# SCH_-_ROBOTIC_ARM.net
KiCad netlist of a schematic drawn in Altium Designer
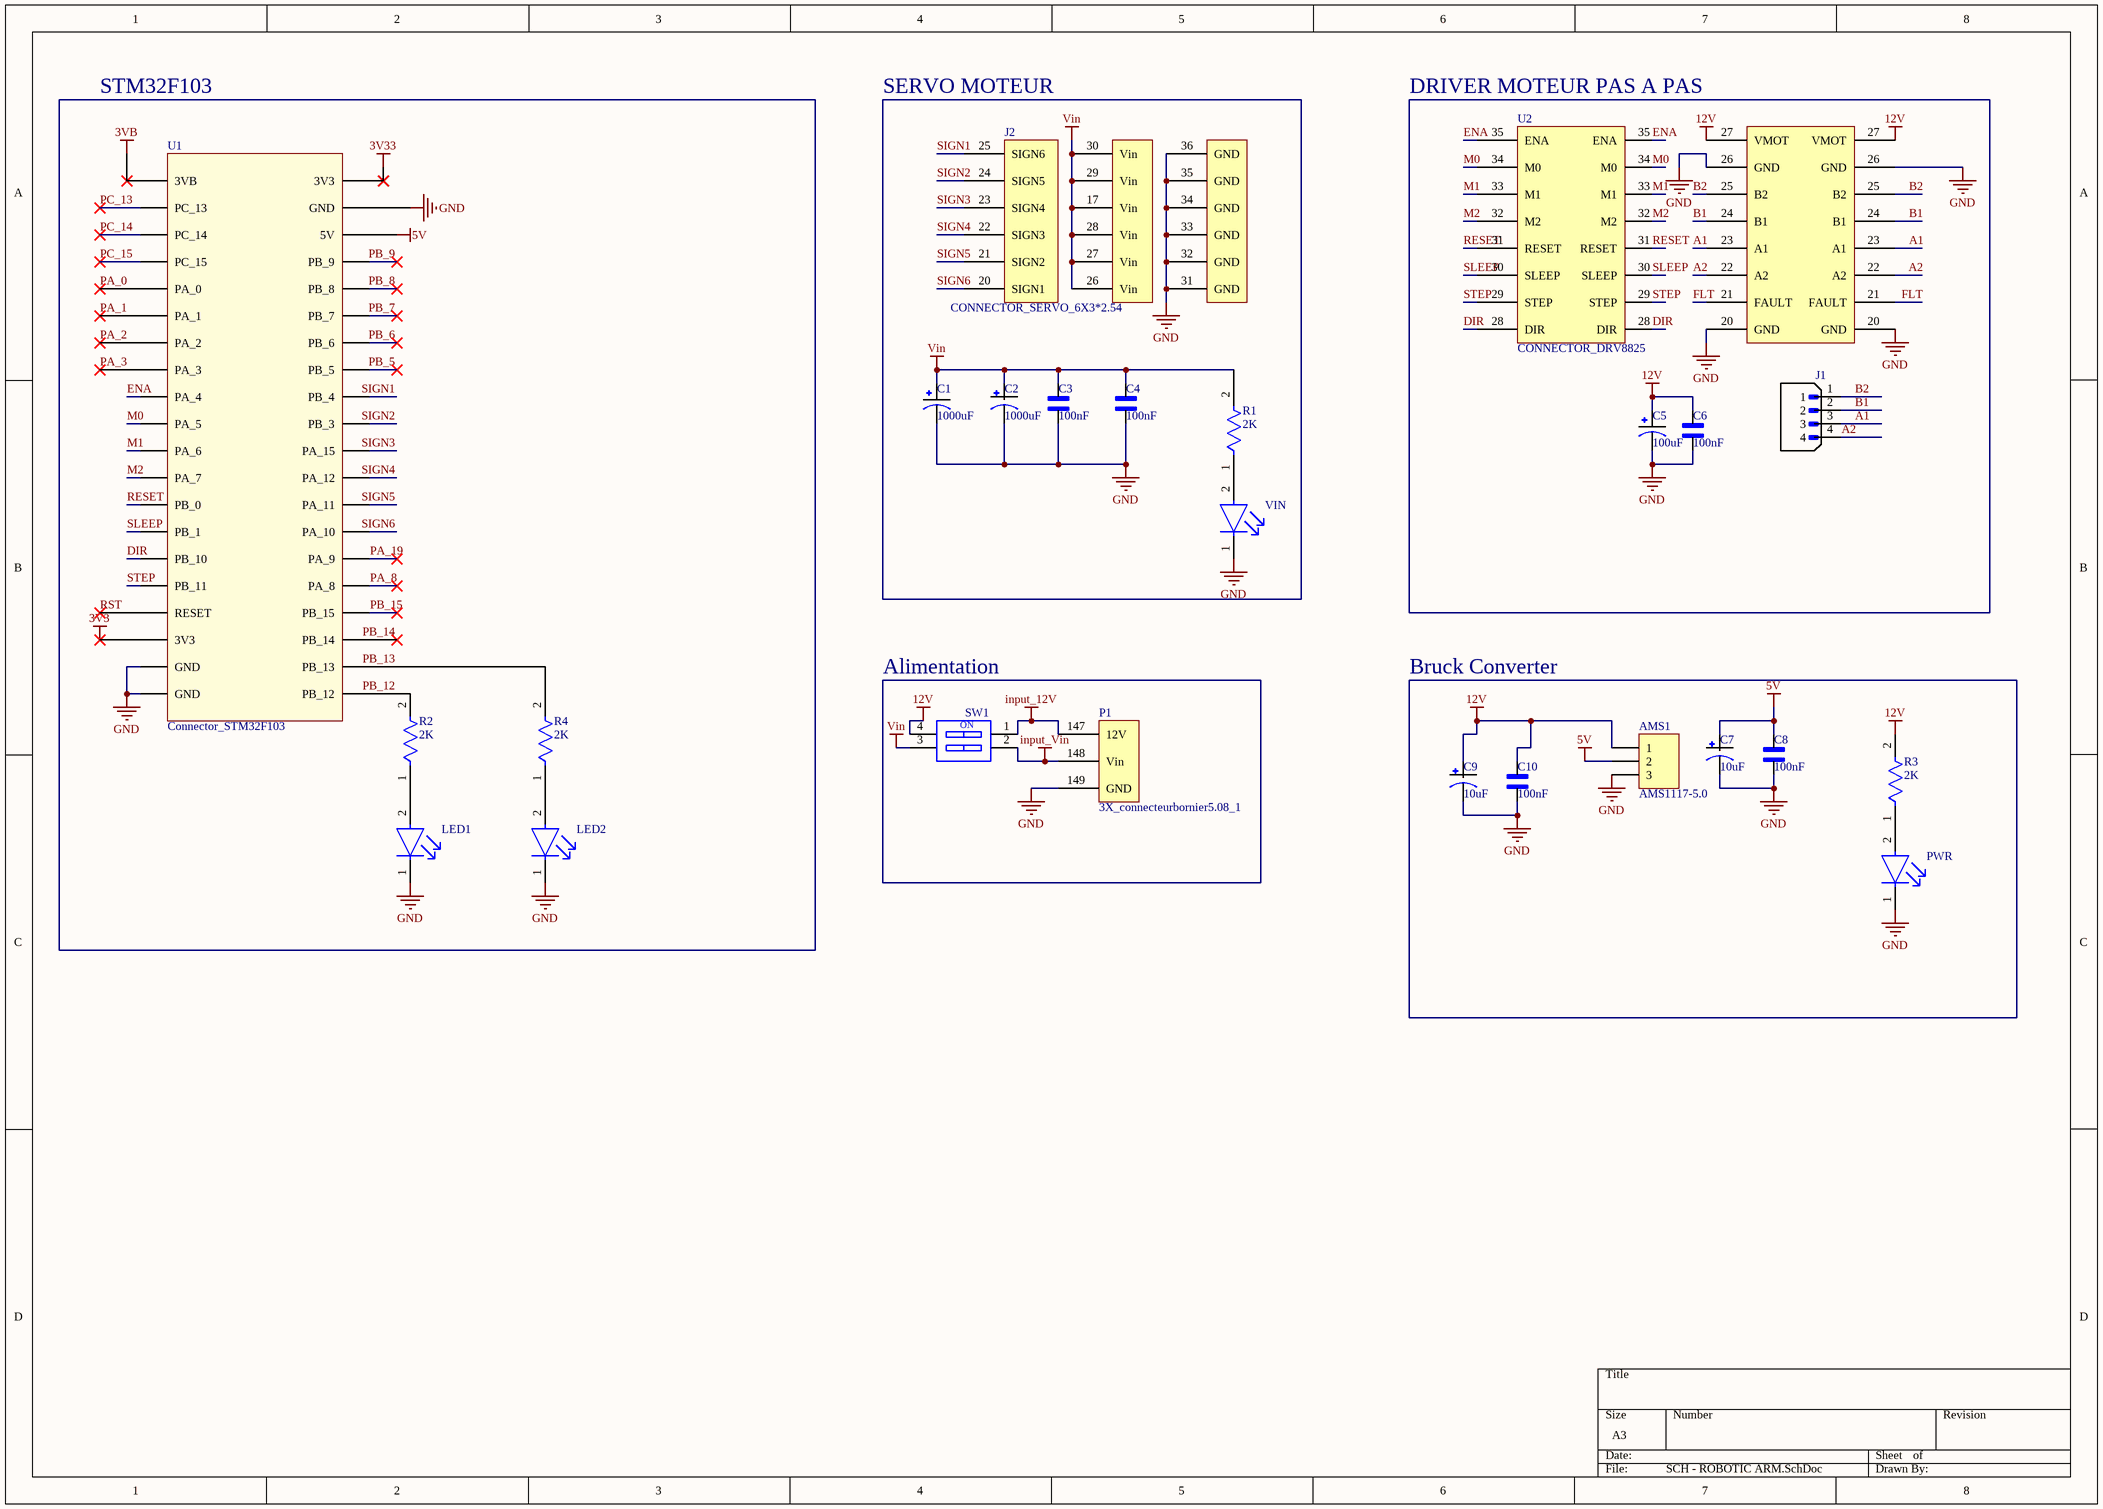
[diagram p0: SCH - ROBOTIC ARM.SchDoc]

(export (version "E")
  (design (tool "Eeschema 10.0.6"))
  (components
    (comp (ref "AMS1")
      (value "AMS1117-5.0")
      (footprint "HDR1X3")
      (description "Header, 3-Pin")
      (fields (field (name "PUBLISHER") "Altium Limited"))
      (libsource (lib "Miscellaneous Connectors") (part "Header 3"))
    )
    (comp (ref "C1")
      (value "1000uF")
      (footprint "*CAPPRD500W60D1000H1600_ECA1CM102(Primary)")
      (description "1000ÂµF 16V Aluminum Electrolytic Capacitors Radial, Can 2000 Hrs @ 85Â°C")
      (fields (field (name "MF") "Panasonic") (field (name "MP") "ECA1CM102"))
      (libsource (lib "Schlib1") (part "ECA1CM102"))
    )
    (comp (ref "C2")
      (value "1000uF")
      (footprint "*CAPPRD200W50D550H1250")
      (description "10 ÂµF 25 V Aluminum Electrolytic Capacitors Radial, Can - 2000 Hrs @ 85Â°C")
      (fields (field (name "MF") "Nichicon") (field (name "MP") "UVR1E100MDD"))
      (libsource (lib "Schlib1") (part "UVR1E100MDD"))
    )
    (comp (ref "C3")
      (value "100nF")
      (footprint "*CAPRR508W50L508T317H508")
      (description "SR Series 5.08x5.08 mm 100 nF 50 V Â±20% Tol. Z5U Radial Lead/SkyCapÂ®")
      (fields (field (name "MF") "AVX") (field (name "MP") "SR215E104MARTR1"))
      (libsource (lib "Schlib1") (part "SR215E104MARTR1"))
    )
    (comp (ref "C4")
      (value "100nF")
      (footprint "*CAPRR508W50L508T317H508")
      (description "SR Series 5.08x5.08 mm 100 nF 50 V Â±20% Tol. Z5U Radial Lead/SkyCapÂ®")
      (fields (field (name "MF") "AVX") (field (name "MP") "SR215E104MARTR1"))
      (libsource (lib "Schlib1") (part "SR215E104MARTR1"))
    )
    (comp (ref "C5")
      (value "100uF")
      (footprint "*CAPPRD500W60D1000H1600_ECA1CM102(Primary)")
      (description "1000ÂµF 16V Aluminum Electrolytic Capacitors Radial, Can 2000 Hrs @ 85Â°C")
      (fields (field (name "MF") "Panasonic") (field (name "MP") "ECA1CM102"))
      (libsource (lib "Schlib1") (part "ECA1CM102"))
    )
    (comp (ref "C6")
      (value "100nF")
      (footprint "*CAPRR508W50L508T317H508")
      (description "SR Series 5.08x5.08 mm 100 nF 50 V Â±20% Tol. Z5U Radial Lead/SkyCapÂ®")
      (fields (field (name "MF") "AVX") (field (name "MP") "SR215E104MARTR1"))
      (libsource (lib "Schlib1") (part "SR215E104MARTR1"))
    )
    (comp (ref "C7")
      (value "10uF")
      (footprint "*CAPPRD200W50D550H1250")
      (description "10 ÂµF 25 V Aluminum Electrolytic Capacitors Radial, Can - 2000 Hrs @ 85Â°C")
      (fields (field (name "MF") "Nichicon") (field (name "MP") "UVR1E100MDD"))
      (libsource (lib "Schlib1") (part "UVR1E100MDD"))
    )
    (comp (ref "C8")
      (value "100nF")
      (footprint "*CAPRR508W50L508T317H508")
      (description "SR Series 5.08x5.08 mm 100 nF 50 V Â±20% Tol. Z5U Radial Lead/SkyCapÂ®")
      (fields (field (name "MF") "AVX") (field (name "MP") "SR215E104MARTR1"))
      (libsource (lib "Schlib1") (part "SR215E104MARTR1"))
    )
    (comp (ref "C9")
      (value "10uF")
      (footprint "*CAPPRD200W50D550H1250")
      (description "10 ÂµF 25 V Aluminum Electrolytic Capacitors Radial, Can - 2000 Hrs @ 85Â°C")
      (fields (field (name "MF") "Nichicon") (field (name "MP") "UVR1E100MDD"))
      (libsource (lib "Schlib1") (part "UVR1E100MDD"))
    )
    (comp (ref "C10")
      (value "100nF")
      (footprint "*CAPPRD200W50D550H1250")
      (description "SR Series 5.08x5.08 mm 100 nF 50 V Â±20% Tol. Z5U Radial Lead/SkyCapÂ®")
      (fields (field (name "MF") "AVX") (field (name "MP") "SR215E104MARTR1"))
      (libsource (lib "Schlib1") (part "SR215E104MARTR1"))
    )
    (comp (ref "J1")
      (value "B4B-XH-A(LF)(SN)")
      (footprint "*JST_B4B-XH-A(LF)(SN)")
      (fields (field (name "MF") "JST") (field (name "MP") "B4B-XH-A  (LF)(SN)"))
      (libsource (lib "Schlib1") (part "B4B-XH-A(LF)(SN)"))
    )
    (comp (ref "J2")
      (value "CONNECTOR_SERVO_6X3*2.54")
      (footprint "CONNECTOR_SERVO_6X3*2.54")
      (libsource (lib "Schlib1") (part "CONNECTOR_SERVO_6X3*2.54"))
    )
    (comp (ref "LED1")
      (value "LED1")
      (footprint "FP-VSLB3940-MFG")
      (description "VSLB3940 940 nm 100 mA ±22° Through Hole High Speed Infrared Emitting Diode - T-1")
      (libsource (lib "Altium Content Vault") (part "8706943c75ba83719d021d2fdc84c58"))
    )
    (comp (ref "LED2")
      (value "LED1")
      (footprint "FP-VSLB3940-MFG")
      (description "VSLB3940 940 nm 100 mA ±22° Through Hole High Speed Infrared Emitting Diode - T-1")
      (libsource (lib "Altium Content Vault") (part "8706943c75ba83719d021d2fdc84c58"))
    )
    (comp (ref "P1")
      (value "3X_connecteurbornier5.08_1")
      (footprint "3X_connecteur_bornier_5.08")
      (libsource (lib "Schlib1") (part "3X_connecteurbornier5.08_1"))
    )
    (comp (ref "PWR")
      (value "LED1")
      (footprint "FP-VSLB3940-MFG")
      (description "VSLB3940 940 nm 100 mA ±22° Through Hole High Speed Infrared Emitting Diode - T-1")
      (libsource (lib "Altium Content Vault") (part "8706943c75ba83719d021d2fdc84c58"))
    )
    (comp (ref "R1")
      (value "2K")
      (footprint "FP-CMF50-0")
      (description "RN50C9532FB14 RN50 Series 0.05 W 95.3 kOhm ± 1% ±50 ppm/°C Axial Metal Film Resistor")
      (fields (field (name "TOLERANCE") "1%"))
      (libsource (lib "Altium Content Vault") (part "1029c3af85768c4190bb7ad29bc67b5"))
    )
    (comp (ref "R2")
      (value "2K")
      (footprint "FP-CMF50-0")
      (description "RN50C9532FB14 RN50 Series 0.05 W 95.3 kOhm ± 1% ±50 ppm/°C Axial Metal Film Resistor")
      (fields (field (name "TOLERANCE") "1%"))
      (libsource (lib "Altium Content Vault") (part "1029c3af85768c4190bb7ad29bc67b5"))
    )
    (comp (ref "R3")
      (value "2K")
      (footprint "FP-CMF50-0")
      (description "RN50C9532FB14 RN50 Series 0.05 W 95.3 kOhm ± 1% ±50 ppm/°C Axial Metal Film Resistor")
      (fields (field (name "TOLERANCE") "1%"))
      (libsource (lib "Altium Content Vault") (part "1029c3af85768c4190bb7ad29bc67b5"))
    )
    (comp (ref "R4")
      (value "2K")
      (footprint "FP-CMF50-0")
      (description "RN50C9532FB14 RN50 Series 0.05 W 95.3 kOhm ± 1% ±50 ppm/°C Axial Metal Film Resistor")
      (fields (field (name "TOLERANCE") "1%"))
      (libsource (lib "Altium Content Vault") (part "1029c3af85768c4190bb7ad29bc67b5"))
    )
    (comp (ref "SW1")
      (value "418117170902")
      (footprint "418117170902")
      (description "Dip Switch, 0.025A, 24Vdc, 2 Pos, Tht Rohs Compliant: Yes")
      (libsource (lib "Altium Content Vault") (part "DIP-2"))
    )
    (comp (ref "U1")
      (value "Connector_STM32F103")
      (footprint "Connector_STM32F103")
      (libsource (lib "Schlib1") (part "Connector_STM32F103"))
    )
    (comp (ref "U2")
      (value "CONNECTOR_DRV8825")
      (footprint "CONNECTOR_DRV8825")
      (libsource (lib "Schlib1") (part "CONNECTOR_DRV8825"))
    )
    (comp (ref "VIN")
      (value "LED1")
      (footprint "FP-VSLB3940-MFG")
      (description "VSLB3940 940 nm 100 mA ±22° Through Hole High Speed Infrared Emitting Diode - T-1")
      (libsource (lib "Altium Content Vault") (part "8706943c75ba83719d021d2fdc84c58"))
    )
  )
  (nets
    (net (code "1") (name "/A1") (class "Default")
      (node (ref "J1") (pin "3") (pinfunction "3_3") (pintype "passive"))
      (node (ref "U2") (pin "23") (pinfunction "A1_23") (pintype "passive"))
    )
    (net (code "2") (name "/A2") (class "Default")
      (node (ref "J1") (pin "4") (pinfunction "4_4") (pintype "passive"))
      (node (ref "U2") (pin "22") (pinfunction "A2_22") (pintype "passive"))
    )
    (net (code "3") (name "/B1") (class "Default")
      (node (ref "J1") (pin "2") (pinfunction "2_2") (pintype "passive"))
      (node (ref "U2") (pin "24") (pinfunction "B1_24") (pintype "passive"))
    )
    (net (code "4") (name "/B2") (class "Default")
      (node (ref "J1") (pin "1") (pinfunction "1_1") (pintype "passive"))
      (node (ref "U2") (pin "25") (pinfunction "B2_25") (pintype "passive"))
    )
    (net (code "5") (name "/DIR") (class "Default")
      (node (ref "U1") (pin "140") (pinfunction "PB_10_140") (pintype "passive"))
      (node (ref "U2") (pin "28") (pinfunction "DIR_28") (pintype "passive"))
    )
    (net (code "6") (name "/ENA") (class "Default")
      (node (ref "U1") (pin "134") (pinfunction "PA_4_134") (pintype "passive"))
      (node (ref "U2") (pin "35") (pinfunction "ENA_35") (pintype "passive"))
    )
    (net (code "7") (name "/FLT") (class "Default")
      (node (ref "U2") (pin "21") (pinfunction "FAULT_21") (pintype "passive"))
    )
    (net (code "8") (name "/M0") (class "Default")
      (node (ref "U1") (pin "135") (pinfunction "PA_5_135") (pintype "passive"))
      (node (ref "U2") (pin "34") (pinfunction "M0_34") (pintype "passive"))
    )
    (net (code "9") (name "/M1") (class "Default")
      (node (ref "U1") (pin "136") (pinfunction "PA_6_136") (pintype "passive"))
      (node (ref "U2") (pin "33") (pinfunction "M1_33") (pintype "passive"))
    )
    (net (code "10") (name "/M2") (class "Default")
      (node (ref "U1") (pin "137") (pinfunction "PA_7_137") (pintype "passive"))
      (node (ref "U2") (pin "32") (pinfunction "M2_32") (pintype "passive"))
    )
    (net (code "11") (name "/PA_0") (class "Default")
      (node (ref "U1") (pin "130") (pinfunction "PA_0_130") (pintype "passive+no_connect"))
    )
    (net (code "12") (name "/PA_1") (class "Default")
      (node (ref "U1") (pin "131") (pinfunction "PA_1_131") (pintype "passive+no_connect"))
    )
    (net (code "13") (name "/PA_2") (class "Default")
      (node (ref "U1") (pin "132") (pinfunction "PA_2_132") (pintype "passive+no_connect"))
    )
    (net (code "14") (name "/PA_3") (class "Default")
      (node (ref "U1") (pin "133") (pinfunction "PA_3_133") (pintype "passive+no_connect"))
    )
    (net (code "15") (name "/PA_8") (class "Default")
      (node (ref "U1") (pin "120") (pinfunction "PA_8_120") (pintype "passive+no_connect"))
    )
    (net (code "16") (name "/PA_19") (class "Default")
      (node (ref "U1") (pin "119") (pinfunction "PA_9_119") (pintype "passive+no_connect"))
    )
    (net (code "17") (name "/PB_5") (class "Default")
      (node (ref "U1") (pin "112") (pinfunction "PB_5_112") (pintype "passive+no_connect"))
    )
    (net (code "18") (name "/PB_6") (class "Default")
      (node (ref "U1") (pin "111") (pinfunction "PB_6_111") (pintype "passive+no_connect"))
    )
    (net (code "19") (name "/PB_7") (class "Default")
      (node (ref "U1") (pin "110") (pinfunction "PB_7_110") (pintype "passive+no_connect"))
    )
    (net (code "20") (name "/PB_8") (class "Default")
      (node (ref "U1") (pin "109") (pinfunction "PB_8_109") (pintype "passive+no_connect"))
    )
    (net (code "21") (name "/PB_9") (class "Default")
      (node (ref "U1") (pin "108") (pinfunction "PB_9_108") (pintype "passive+no_connect"))
    )
    (net (code "22") (name "/PB_12") (class "Default")
      (node (ref "R2") (pin "2") (pinfunction "2_2") (pintype "passive"))
      (node (ref "U1") (pin "124") (pinfunction "PB_12_124") (pintype "passive"))
    )
    (net (code "23") (name "/PB_13") (class "Default")
      (node (ref "R4") (pin "2") (pinfunction "2_2") (pintype "passive"))
      (node (ref "U1") (pin "123") (pinfunction "PB_13_123") (pintype "passive"))
    )
    (net (code "24") (name "/PB_14") (class "Default")
      (node (ref "U1") (pin "122") (pinfunction "PB_14_122") (pintype "passive+no_connect"))
    )
    (net (code "25") (name "/PB_15") (class "Default")
      (node (ref "U1") (pin "121") (pinfunction "PB_15_121") (pintype "passive+no_connect"))
    )
    (net (code "26") (name "/PC_13") (class "Default")
      (node (ref "U1") (pin "127") (pinfunction "PC_13_127") (pintype "passive+no_connect"))
    )
    (net (code "27") (name "/PC_14") (class "Default")
      (node (ref "U1") (pin "128") (pinfunction "PC_14_128") (pintype "passive+no_connect"))
    )
    (net (code "28") (name "/PC_15") (class "Default")
      (node (ref "U1") (pin "129") (pinfunction "PC_15_129") (pintype "passive+no_connect"))
    )
    (net (code "29") (name "/RESET") (class "Default")
      (node (ref "U1") (pin "138") (pinfunction "PB_0_138") (pintype "passive"))
      (node (ref "U2") (pin "31") (pinfunction "RESET_31") (pintype "passive"))
    )
    (net (code "30") (name "/RST") (class "Default")
      (node (ref "U1") (pin "142") (pinfunction "RESET_142") (pintype "passive+no_connect"))
    )
    (net (code "31") (name "/SIGN1") (class "Default")
      (node (ref "J2") (pin "25") (pinfunction "SIGN6_25") (pintype "passive"))
      (node (ref "U1") (pin "113") (pinfunction "PB_4_113") (pintype "passive"))
    )
    (net (code "32") (name "/SIGN2") (class "Default")
      (node (ref "J2") (pin "24") (pinfunction "SIGN5_24") (pintype "passive"))
      (node (ref "U1") (pin "114") (pinfunction "PB_3_114") (pintype "passive"))
    )
    (net (code "33") (name "/SIGN3") (class "Default")
      (node (ref "J2") (pin "23") (pinfunction "SIGN4_23") (pintype "passive"))
      (node (ref "U1") (pin "115") (pinfunction "PA_15_115") (pintype "passive"))
    )
    (net (code "34") (name "/SIGN4") (class "Default")
      (node (ref "J2") (pin "22") (pinfunction "SIGN3_22") (pintype "passive"))
      (node (ref "U1") (pin "116") (pinfunction "PA_12_116") (pintype "passive"))
    )
    (net (code "35") (name "/SIGN5") (class "Default")
      (node (ref "J2") (pin "21") (pinfunction "SIGN2_21") (pintype "passive"))
      (node (ref "U1") (pin "117") (pinfunction "PA_11_117") (pintype "passive"))
    )
    (net (code "36") (name "/SIGN6") (class "Default")
      (node (ref "J2") (pin "20") (pinfunction "SIGN1_20") (pintype "passive"))
      (node (ref "U1") (pin "118") (pinfunction "PA_10_118") (pintype "passive"))
    )
    (net (code "37") (name "/SLEEP") (class "Default")
      (node (ref "U1") (pin "139") (pinfunction "PB_1_139") (pintype "passive"))
      (node (ref "U2") (pin "30") (pinfunction "SLEEP_30") (pintype "passive"))
    )
    (net (code "38") (name "/STEP") (class "Default")
      (node (ref "U1") (pin "141") (pinfunction "PB_11_141") (pintype "passive"))
      (node (ref "U2") (pin "29") (pinfunction "STEP_29") (pintype "passive"))
    )
    (net (code "39") (name "3V3") (class "Default")
      (node (ref "U1") (pin "143") (pinfunction "3V3_143") (pintype "passive"))
    )
    (net (code "40") (name "3V33") (class "Default")
      (node (ref "U1") (pin "105") (pinfunction "3V3_105") (pintype "passive"))
    )
    (net (code "41") (name "3VB") (class "Default")
      (node (ref "U1") (pin "126") (pinfunction "3VB_126") (pintype "passive"))
    )
    (net (code "42") (name "5V") (class "Default")
      (node (ref "AMS1") (pin "2") (pinfunction "2_2") (pintype "passive"))
      (node (ref "C7") (pin "1") (pinfunction "1_1") (pintype "passive"))
      (node (ref "C8") (pin "1") (pinfunction "1_1") (pintype "passive"))
      (node (ref "U1") (pin "107") (pinfunction "5V_107") (pintype "passive"))
    )
    (net (code "43") (name "12V") (class "Default")
      (node (ref "AMS1") (pin "1") (pinfunction "1_1") (pintype "passive"))
      (node (ref "C10") (pin "1") (pinfunction "1_1") (pintype "passive"))
      (node (ref "C5") (pin "P") (pinfunction "P_P") (pintype "passive"))
      (node (ref "C6") (pin "1") (pinfunction "1_1") (pintype "passive"))
      (node (ref "C9") (pin "1") (pinfunction "1_1") (pintype "passive"))
      (node (ref "R3") (pin "2") (pinfunction "2_2") (pintype "passive"))
      (node (ref "SW1") (pin "4") (pinfunction "4_4") (pintype "passive"))
      (node (ref "U2") (pin "27") (pinfunction "VMOT_27") (pintype "passive"))
    )
    (net (code "44") (name "GND") (class "Default")
      (node (ref "AMS1") (pin "3") (pinfunction "3_3") (pintype "passive"))
      (node (ref "C1") (pin "N") (pinfunction "N_N") (pintype "passive"))
      (node (ref "C10") (pin "2") (pinfunction "2_2") (pintype "passive"))
      (node (ref "C2") (pin "2") (pinfunction "2_2") (pintype "passive"))
      (node (ref "C3") (pin "2") (pinfunction "2_2") (pintype "passive"))
      (node (ref "C4") (pin "2") (pinfunction "2_2") (pintype "passive"))
      (node (ref "C5") (pin "N") (pinfunction "N_N") (pintype "passive"))
      (node (ref "C6") (pin "2") (pinfunction "2_2") (pintype "passive"))
      (node (ref "C7") (pin "2") (pinfunction "2_2") (pintype "passive"))
      (node (ref "C8") (pin "2") (pinfunction "2_2") (pintype "passive"))
      (node (ref "C9") (pin "2") (pinfunction "2_2") (pintype "passive"))
      (node (ref "J2") (pin "31") (pinfunction "GND_31") (pintype "passive"))
      (node (ref "J2") (pin "32") (pinfunction "GND_32") (pintype "passive"))
      (node (ref "J2") (pin "33") (pinfunction "GND_33") (pintype "passive"))
      (node (ref "J2") (pin "34") (pinfunction "GND_34") (pintype "passive"))
      (node (ref "J2") (pin "35") (pinfunction "GND_35") (pintype "passive"))
      (node (ref "J2") (pin "36") (pinfunction "GND_36") (pintype "passive"))
      (node (ref "LED1") (pin "1") (pinfunction "C_1") (pintype "passive"))
      (node (ref "LED2") (pin "1") (pinfunction "C_1") (pintype "passive"))
      (node (ref "P1") (pin "149") (pinfunction "GND_149") (pintype "passive"))
      (node (ref "PWR") (pin "1") (pinfunction "C_1") (pintype "passive"))
      (node (ref "U1") (pin "106") (pinfunction "GND_106") (pintype "passive"))
      (node (ref "U1") (pin "144") (pinfunction "GND_144") (pintype "passive"))
      (node (ref "U1") (pin "145") (pinfunction "GND_145") (pintype "passive"))
      (node (ref "U2") (pin "20") (pinfunction "GND_20") (pintype "passive"))
      (node (ref "U2") (pin "26") (pinfunction "GND_26") (pintype "passive"))
      (node (ref "VIN") (pin "1") (pinfunction "C_1") (pintype "passive"))
    )
    (net (code "45") (name "Net-(LED1-A)") (class "Default")
      (node (ref "LED1") (pin "2") (pinfunction "A_2") (pintype "passive"))
      (node (ref "R2") (pin "1") (pinfunction "1_1") (pintype "passive"))
    )
    (net (code "46") (name "Net-(LED2-A)") (class "Default")
      (node (ref "LED2") (pin "2") (pinfunction "A_2") (pintype "passive"))
      (node (ref "R4") (pin "1") (pinfunction "1_1") (pintype "passive"))
    )
    (net (code "47") (name "Net-(PWR-A)") (class "Default")
      (node (ref "PWR") (pin "2") (pinfunction "A_2") (pintype "passive"))
      (node (ref "R3") (pin "1") (pinfunction "1_1") (pintype "passive"))
    )
    (net (code "48") (name "Net-(VIN-A)") (class "Default")
      (node (ref "R1") (pin "1") (pinfunction "1_1") (pintype "passive"))
      (node (ref "VIN") (pin "2") (pinfunction "A_2") (pintype "passive"))
    )
    (net (code "49") (name "Vin") (class "Default")
      (node (ref "C1") (pin "P") (pinfunction "P_P") (pintype "passive"))
      (node (ref "C2") (pin "1") (pinfunction "1_1") (pintype "passive"))
      (node (ref "C3") (pin "1") (pinfunction "1_1") (pintype "passive"))
      (node (ref "C4") (pin "1") (pinfunction "1_1") (pintype "passive"))
      (node (ref "J2") (pin "17") (pinfunction "Vin_17") (pintype "passive"))
      (node (ref "J2") (pin "26") (pinfunction "Vin_26") (pintype "passive"))
      (node (ref "J2") (pin "27") (pinfunction "Vin_27") (pintype "passive"))
      (node (ref "J2") (pin "28") (pinfunction "Vin_28") (pintype "passive"))
      (node (ref "J2") (pin "29") (pinfunction "Vin_29") (pintype "passive"))
      (node (ref "J2") (pin "30") (pinfunction "Vin_30") (pintype "passive"))
      (node (ref "R1") (pin "2") (pinfunction "2_2") (pintype "passive"))
      (node (ref "SW1") (pin "3") (pinfunction "3_3") (pintype "passive"))
    )
    (net (code "50") (name "input_12V") (class "Default")
      (node (ref "P1") (pin "147") (pinfunction "12V_147") (pintype "passive"))
      (node (ref "SW1") (pin "1") (pinfunction "1_1") (pintype "passive"))
    )
    (net (code "51") (name "input_Vin") (class "Default")
      (node (ref "P1") (pin "148") (pinfunction "Vin_148") (pintype "passive"))
      (node (ref "SW1") (pin "2") (pinfunction "2_2") (pintype "passive"))
    )
  )
)
